# LCD.net
KiCad netlist of a schematic drawn in Altium Designer
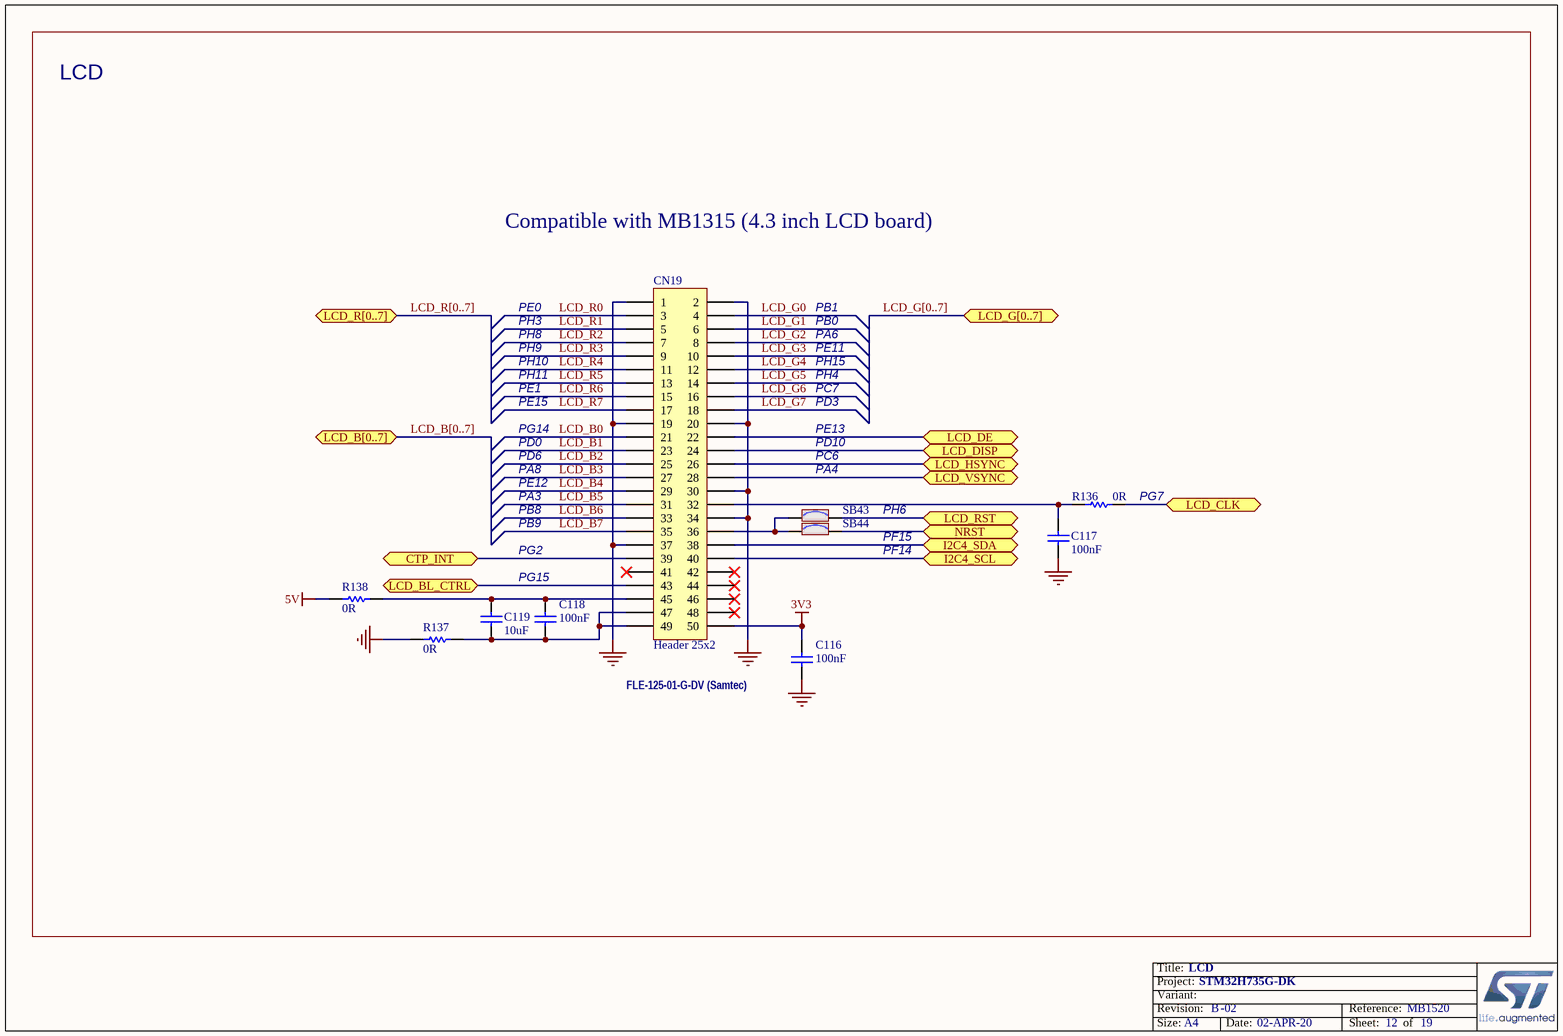
[diagram p0: LCD.SchDoc]

(export (version "E")
  (design (tool "Eeschema 10.0.6"))
  (components
    (comp (ref "C116")
      (value "100nF")
      (footprint "C0402")
      (description "Capacitor, MLCC, 100nF, 16V, X7R, 10%, 0402, T=0.5mm")
      (fields
        (field (name "INTERNAL_PART_NUMBER") "MCD-00006")
        (field (name "MANUFACTURER_PART_NUMBER") "CC0402KRX7R7BB104")
        (field (name "PROVIDED_BY") "Subcon")
      )
      (libsource (lib "MCD_PARTS_database") (part "Capacitor"))
    )
    (comp (ref "C117")
      (value "100nF")
      (footprint "C0402")
      (description "Capacitor, MLCC, 100nF, 16V, X7R, 10%, 0402, T=0.5mm")
      (fields
        (field (name "INTERNAL_PART_NUMBER") "MCD-00006")
        (field (name "MANUFACTURER_PART_NUMBER") "CC0402KRX7R7BB104")
        (field (name "PROVIDED_BY") "Subcon")
      )
      (libsource (lib "MCD_PARTS_database") (part "Capacitor"))
    )
    (comp (ref "C118")
      (value "100nF")
      (footprint "C0402")
      (description "Capacitor, MLCC, 100nF, 16V, X7R, 10%, 0402, T=0.5mm")
      (fields
        (field (name "INTERNAL_PART_NUMBER") "MCD-00006")
        (field (name "MANUFACTURER_PART_NUMBER") "CC0402KRX7R7BB104")
        (field (name "PROVIDED_BY") "Subcon")
      )
      (libsource (lib "MCD_PARTS_database") (part "Capacitor"))
    )
    (comp (ref "C119")
      (value "10uF")
      (footprint "C0805")
      (description "Capacitor, MLCC, 10uF, 25V, X5R, 10%, 0805, T=0,85mm")
      (fields
        (field (name "INTERNAL_PART_NUMBER") "MCD-00014")
        (field (name "MANUFACTURER_PART_NUMBER") "CC0805KRX5R8BB106")
        (field (name "PROVIDED_BY") "Subcon")
      )
      (libsource (lib "MCD_PARTS_database") (part "Capacitor"))
    )
    (comp (ref "CN19")
      (value "Header 25x2")
      (footprint "MOD_LCD_MB1046B__CON_SAMTEC_FLE-125-01-G-DV")
      (description "Header 25x2 for MB1046 - LCD 4.3 inches daughter board")
      (fields
        (field (name "INTERNAL_PART_NUMBER") "MCD-01222")
        (field (name "MANUFACTURER_PART_NUMBER") "FLE-125-01-G-DV")
        (field (name "PROVIDED_BY") "SUBCO")
      )
      (libsource (lib "MCD_PARTS_database") (part "Header 25x2"))
    )
    (comp (ref "R136")
      (value "0R")
      (footprint "R0402")
      (description "Resistor,0R,0402,5%,1/16W")
      (fields
        (field (name "INTERNAL_PART_NUMBER") "MCD-00052")
        (field (name "MANUFACTURER_PART_NUMBER") "RC0402JR-070RL")
        (field (name "PROVIDED_BY") "SUBCO")
      )
      (libsource (lib "MCD_PARTS_database") (part "Resistor"))
    )
    (comp (ref "R137")
      (value "0R")
      (footprint "R0603")
      (description "Resistor,0R,0603,5%,1/10W")
      (fields
        (field (name "INTERNAL_PART_NUMBER") "MCD-00056")
        (field (name "MANUFACTURER_PART_NUMBER") "RC0603JR-070RL")
        (field (name "PROVIDED_BY") "subcon")
      )
      (libsource (lib "MCD_PARTS_database") (part "Resistor"))
    )
    (comp (ref "R138")
      (value "0R")
      (footprint "R0603")
      (description "Resistor,0R,0603,5%,1/10W")
      (fields
        (field (name "INTERNAL_PART_NUMBER") "MCD-00056")
        (field (name "MANUFACTURER_PART_NUMBER") "RC0603JR-070RL")
        (field (name "PROVIDED_BY") "subcon")
      )
      (libsource (lib "MCD_PARTS_database") (part "Resistor"))
    )
    (comp (ref "SB43")
      (value "SB_ON")
      (footprint "SOLDER-BRIDGE_R0603-0R")
      (description "Solder Bridge ON")
      (fields
        (field (name "INTERNAL_PART_NUMBER") "MCD-00071")
        (field (name "MANUFACTURER_PART_NUMBER") "RC0603JR-070RL")
        (field (name "PROVIDED_BY") "SUBCO")
      )
      (libsource (lib "MCD_PARTS_database") (part "SB_ON"))
    )
    (comp (ref "SB44")
      (value "SB_ON")
      (footprint "SOLDER-BRIDGE_R0603-0R")
      (description "Solder Bridge ON")
      (fields
        (field (name "INTERNAL_PART_NUMBER") "MCD-00071")
        (field (name "MANUFACTURER_PART_NUMBER") "RC0603JR-070RL")
        (field (name "PROVIDED_BY") "SUBCO")
      )
      (libsource (lib "MCD_PARTS_database") (part "SB_ON"))
    )
  )
  (nets
    (net (code "1") (name "/CTP_INT") (class "Default")
      (node (ref "CN19") (pin "39") (pinfunction "39_39") (pintype "passive"))
    )
    (net (code "2") (name "/I2C4_SCL") (class "Default")
      (node (ref "CN19") (pin "40") (pinfunction "40_40") (pintype "passive"))
    )
    (net (code "3") (name "/I2C4_SDA") (class "Default")
      (node (ref "CN19") (pin "38") (pinfunction "38_38") (pintype "passive"))
    )
    (net (code "4") (name "/LCD_B0") (class "Default")
      (node (ref "CN19") (pin "21") (pinfunction "21_21") (pintype "passive"))
    )
    (net (code "5") (name "/LCD_B1") (class "Default")
      (node (ref "CN19") (pin "23") (pinfunction "23_23") (pintype "passive"))
    )
    (net (code "6") (name "/LCD_B2") (class "Default")
      (node (ref "CN19") (pin "25") (pinfunction "25_25") (pintype "passive"))
    )
    (net (code "7") (name "/LCD_B3") (class "Default")
      (node (ref "CN19") (pin "27") (pinfunction "27_27") (pintype "passive"))
    )
    (net (code "8") (name "/LCD_B4") (class "Default")
      (node (ref "CN19") (pin "29") (pinfunction "29_29") (pintype "passive"))
    )
    (net (code "9") (name "/LCD_B5") (class "Default")
      (node (ref "CN19") (pin "31") (pinfunction "31_31") (pintype "passive"))
    )
    (net (code "10") (name "/LCD_B6") (class "Default")
      (node (ref "CN19") (pin "33") (pinfunction "33_33") (pintype "passive"))
    )
    (net (code "11") (name "/LCD_B7") (class "Default")
      (node (ref "CN19") (pin "35") (pinfunction "35_35") (pintype "passive"))
    )
    (net (code "12") (name "/LCD_BL_CTRL") (class "Default")
      (node (ref "CN19") (pin "43") (pinfunction "43_43") (pintype "passive"))
    )
    (net (code "14") (name "/LCD_CLK") (class "Default")
      (node (ref "R136") (pin "2") (pinfunction "2_2") (pintype "passive"))
    )
    (net (code "15") (name "/LCD_DE") (class "Default")
      (node (ref "CN19") (pin "22") (pinfunction "22_22") (pintype "passive"))
    )
    (net (code "16") (name "/LCD_DISP") (class "Default")
      (node (ref "CN19") (pin "24") (pinfunction "24_24") (pintype "passive"))
    )
    (net (code "17") (name "/LCD_G0") (class "Default")
      (node (ref "CN19") (pin "4") (pinfunction "4_4") (pintype "passive"))
    )
    (net (code "18") (name "/LCD_G1") (class "Default")
      (node (ref "CN19") (pin "6") (pinfunction "6_6") (pintype "passive"))
    )
    (net (code "19") (name "/LCD_G2") (class "Default")
      (node (ref "CN19") (pin "8") (pinfunction "8_8") (pintype "passive"))
    )
    (net (code "20") (name "/LCD_G3") (class "Default")
      (node (ref "CN19") (pin "10") (pinfunction "10_10") (pintype "passive"))
    )
    (net (code "21") (name "/LCD_G4") (class "Default")
      (node (ref "CN19") (pin "12") (pinfunction "12_12") (pintype "passive"))
    )
    (net (code "22") (name "/LCD_G5") (class "Default")
      (node (ref "CN19") (pin "14") (pinfunction "14_14") (pintype "passive"))
    )
    (net (code "23") (name "/LCD_G6") (class "Default")
      (node (ref "CN19") (pin "16") (pinfunction "16_16") (pintype "passive"))
    )
    (net (code "24") (name "/LCD_G7") (class "Default")
      (node (ref "CN19") (pin "18") (pinfunction "18_18") (pintype "passive"))
    )
    (net (code "26") (name "/LCD_HSYNC") (class "Default")
      (node (ref "CN19") (pin "26") (pinfunction "26_26") (pintype "passive"))
    )
    (net (code "27") (name "/LCD_R0") (class "Default")
      (node (ref "CN19") (pin "3") (pinfunction "3_3") (pintype "passive"))
    )
    (net (code "28") (name "/LCD_R1") (class "Default")
      (node (ref "CN19") (pin "5") (pinfunction "5_5") (pintype "passive"))
    )
    (net (code "29") (name "/LCD_R2") (class "Default")
      (node (ref "CN19") (pin "7") (pinfunction "7_7") (pintype "passive"))
    )
    (net (code "30") (name "/LCD_R3") (class "Default")
      (node (ref "CN19") (pin "9") (pinfunction "9_9") (pintype "passive"))
    )
    (net (code "31") (name "/LCD_R4") (class "Default")
      (node (ref "CN19") (pin "11") (pinfunction "11_11") (pintype "passive"))
    )
    (net (code "32") (name "/LCD_R5") (class "Default")
      (node (ref "CN19") (pin "13") (pinfunction "13_13") (pintype "passive"))
    )
    (net (code "33") (name "/LCD_R6") (class "Default")
      (node (ref "CN19") (pin "15") (pinfunction "15_15") (pintype "passive"))
    )
    (net (code "34") (name "/LCD_R7") (class "Default")
      (node (ref "CN19") (pin "17") (pinfunction "17_17") (pintype "passive"))
    )
    (net (code "35") (name "/LCD_RST") (class "Default")
      (node (ref "SB43") (pin "2") (pinfunction "2_2") (pintype "passive"))
    )
    (net (code "37") (name "/LCD_VSYNC") (class "Default")
      (node (ref "CN19") (pin "28") (pinfunction "28_28") (pintype "passive"))
    )
    (net (code "38") (name "/NRST") (class "Default")
      (node (ref "SB44") (pin "2") (pinfunction "2_2") (pintype "passive"))
    )
    (net (code "39") (name "3V3") (class "Default")
      (node (ref "C116") (pin "1") (pinfunction "1_1") (pintype "passive"))
      (node (ref "CN19") (pin "50") (pinfunction "50_50") (pintype "passive"))
    )
    (net (code "40") (name "5V") (class "Default")
      (node (ref "R138") (pin "1") (pinfunction "1_1") (pintype "passive"))
    )
    (net (code "41") (name "GND") (class "Default")
      (node (ref "C116") (pin "2") (pinfunction "2_2") (pintype "passive"))
      (node (ref "C117") (pin "1") (pinfunction "1_1") (pintype "passive"))
      (node (ref "CN19") (pin "1") (pinfunction "1_1") (pintype "passive"))
      (node (ref "CN19") (pin "19") (pinfunction "19_19") (pintype "passive"))
      (node (ref "CN19") (pin "2") (pinfunction "2_2") (pintype "passive"))
      (node (ref "CN19") (pin "20") (pinfunction "20_20") (pintype "passive"))
      (node (ref "CN19") (pin "30") (pinfunction "30_30") (pintype "passive"))
      (node (ref "CN19") (pin "34") (pinfunction "34_34") (pintype "passive"))
      (node (ref "CN19") (pin "37") (pinfunction "37_37") (pintype "passive"))
      (node (ref "R137") (pin "1") (pinfunction "1_1") (pintype "passive"))
    )
    (net (code "42") (name "Net-(C117-Pad2)") (class "Default")
      (node (ref "C117") (pin "2") (pinfunction "2_2") (pintype "passive"))
      (node (ref "CN19") (pin "32") (pinfunction "32_32") (pintype "passive"))
      (node (ref "R136") (pin "1") (pinfunction "1_1") (pintype "passive"))
    )
    (net (code "43") (name "Net-(C118-Pad1)") (class "Default")
      (node (ref "C118") (pin "1") (pinfunction "1_1") (pintype "passive"))
      (node (ref "C119") (pin "2") (pinfunction "2_2") (pintype "passive"))
      (node (ref "CN19") (pin "45") (pinfunction "45_45") (pintype "passive"))
      (node (ref "R138") (pin "2") (pinfunction "2_2") (pintype "passive"))
    )
    (net (code "44") (name "Net-(C118-Pad2)") (class "Default")
      (node (ref "C118") (pin "2") (pinfunction "2_2") (pintype "passive"))
      (node (ref "C119") (pin "1") (pinfunction "1_1") (pintype "passive"))
      (node (ref "CN19") (pin "47") (pinfunction "47_47") (pintype "passive"))
      (node (ref "CN19") (pin "49") (pinfunction "49_49") (pintype "passive"))
      (node (ref "R137") (pin "2") (pinfunction "2_2") (pintype "passive"))
    )
    (net (code "45") (name "Net-(CN19-Pad36)") (class "Default")
      (node (ref "CN19") (pin "36") (pinfunction "36_36") (pintype "passive"))
      (node (ref "SB43") (pin "1") (pinfunction "1_1") (pintype "passive"))
      (node (ref "SB44") (pin "1") (pinfunction "1_1") (pintype "passive"))
    )
    (net (code "46") (name "unconnected-(CN19-Pad41)") (class "Default")
      (node (ref "CN19") (pin "41") (pinfunction "41_41") (pintype "passive+no_connect"))
    )
    (net (code "47") (name "unconnected-(CN19-Pad42)") (class "Default")
      (node (ref "CN19") (pin "42") (pinfunction "42_42") (pintype "passive+no_connect"))
    )
    (net (code "48") (name "unconnected-(CN19-Pad44)") (class "Default")
      (node (ref "CN19") (pin "44") (pinfunction "44_44") (pintype "passive+no_connect"))
    )
    (net (code "49") (name "unconnected-(CN19-Pad46)") (class "Default")
      (node (ref "CN19") (pin "46") (pinfunction "46_46") (pintype "passive+no_connect"))
    )
    (net (code "50") (name "unconnected-(CN19-Pad48)") (class "Default")
      (node (ref "CN19") (pin "48") (pinfunction "48_48") (pintype "passive+no_connect"))
    )
  )
)
